# MCU-power.net
KiCad netlist of a schematic drawn in Altium Designer
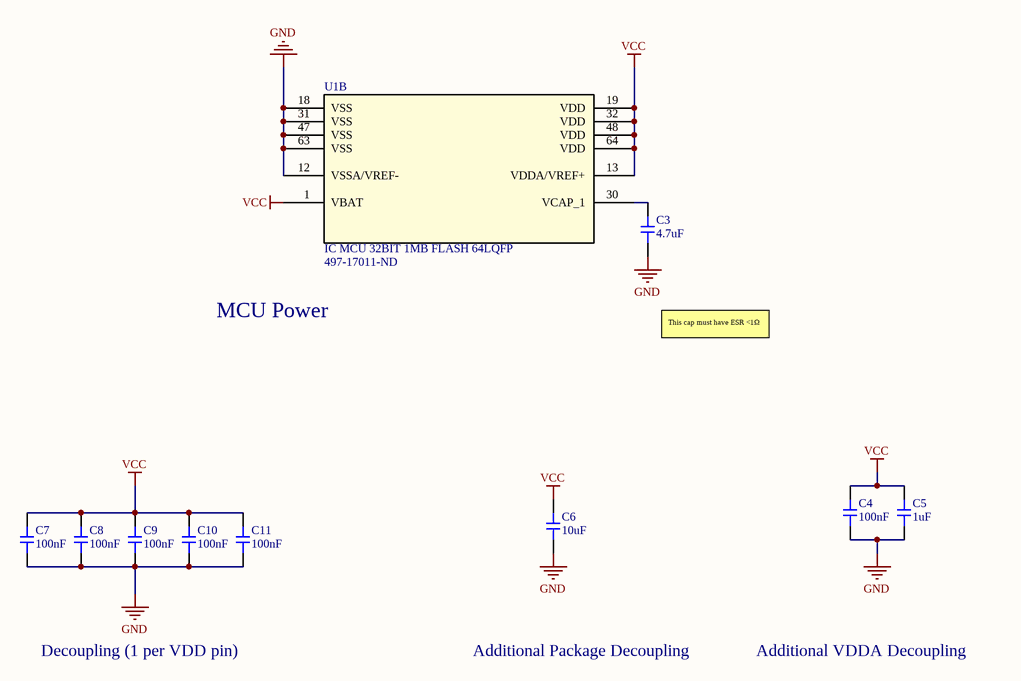
[diagram p0: MCU-power.SchDoc]

(export (version "E")
  (design (tool "Eeschema 10.0.6"))
  (components
    (comp (ref "C3")
      (value "CL10A475KO8NNNC")
      (footprint "CAP-0603")
      (description "Capacitor, Ceramic (MLCC), 4.7uF, ±10%, 16V, X5R, ±10%, SMD 0603")
      (fields
        (field (name "JLCPCB BASIC PART") "Yes")
        (field (name "JLCPCB PART NUMBER") "C19666")
        (field (name "CAPACITANCE") "4.7uF")
      )
      (libsource (lib "JLCCapacitor") (part "CL10A475KO8NNNC"))
    )
    (comp (ref "C4")
      (value "CC0603KRX7R9BB104")
      (footprint "CAP-0603")
      (description "Capacitor, Ceramic (MLCC), 100nF, ±10%, 50V, X7R, ±10%, SMD 0603")
      (fields
        (field (name "JLCPCB BASIC PART") "Yes")
        (field (name "CAPACITANCE") "100nF")
        (field (name "JLCPCB PART NUMBER") "C14663")
      )
      (libsource (lib "JLCCapacitor") (part "CC0603KRX7R9BB104"))
    )
    (comp (ref "C5")
      (value "CL10A105KB8NNNC")
      (footprint "CAP-0603")
      (description "Capacitor, Ceramic (MLCC), 1uF, ±10%, 50V, X5R, ±10%, SMD 0603")
      (fields
        (field (name "JLCPCB BASIC PART") "Yes")
        (field (name "JLCPCB PART NUMBER") "C15849")
        (field (name "CAPACITANCE") "1uF")
      )
      (libsource (lib "JLCCapacitor") (part "CL10A105KB8NNNC"))
    )
    (comp (ref "C6")
      (value "CL10A106KP8NNNC")
      (footprint "CAP-0603")
      (description "Capacitor, Ceramic (MLCC), 10uF, ±10%, 10V, X5R, ±10%, SMD 0603")
      (fields
        (field (name "JLCPCB BASIC PART") "Yes")
        (field (name "JLCPCB PART NUMBER") "C19702")
        (field (name "CAPACITANCE") "10uF")
      )
      (libsource (lib "JLCCapacitor") (part "CL10A106KP8NNNC"))
    )
    (comp (ref "C7")
      (value "CC0603KRX7R9BB104")
      (footprint "CAP-0603")
      (description "Capacitor, Ceramic (MLCC), 100nF, ±10%, 50V, X7R, ±10%, SMD 0603")
      (fields
        (field (name "JLCPCB BASIC PART") "Yes")
        (field (name "CAPACITANCE") "100nF")
        (field (name "JLCPCB PART NUMBER") "C14663")
      )
      (libsource (lib "JLCCapacitor") (part "CC0603KRX7R9BB104"))
    )
    (comp (ref "C8")
      (value "CC0603KRX7R9BB104")
      (footprint "CAP-0603")
      (description "Capacitor, Ceramic (MLCC), 100nF, ±10%, 50V, X7R, ±10%, SMD 0603")
      (fields
        (field (name "JLCPCB BASIC PART") "Yes")
        (field (name "CAPACITANCE") "100nF")
        (field (name "JLCPCB PART NUMBER") "C14663")
      )
      (libsource (lib "JLCCapacitor") (part "CC0603KRX7R9BB104"))
    )
    (comp (ref "C9")
      (value "CC0603KRX7R9BB104")
      (footprint "CAP-0603")
      (description "Capacitor, Ceramic (MLCC), 100nF, ±10%, 50V, X7R, ±10%, SMD 0603")
      (fields
        (field (name "JLCPCB BASIC PART") "Yes")
        (field (name "CAPACITANCE") "100nF")
        (field (name "JLCPCB PART NUMBER") "C14663")
      )
      (libsource (lib "JLCCapacitor") (part "CC0603KRX7R9BB104"))
    )
    (comp (ref "C10")
      (value "CC0603KRX7R9BB104")
      (footprint "CAP-0603")
      (description "Capacitor, Ceramic (MLCC), 100nF, ±10%, 50V, X7R, ±10%, SMD 0603")
      (fields
        (field (name "JLCPCB BASIC PART") "Yes")
        (field (name "CAPACITANCE") "100nF")
        (field (name "JLCPCB PART NUMBER") "C14663")
      )
      (libsource (lib "JLCCapacitor") (part "CC0603KRX7R9BB104"))
    )
    (comp (ref "C11")
      (value "CC0603KRX7R9BB104")
      (footprint "CAP-0603")
      (description "Capacitor, Ceramic (MLCC), 100nF, ±10%, 50V, X7R, ±10%, SMD 0603")
      (fields
        (field (name "JLCPCB BASIC PART") "Yes")
        (field (name "CAPACITANCE") "100nF")
        (field (name "JLCPCB PART NUMBER") "C14663")
      )
      (libsource (lib "JLCCapacitor") (part "CC0603KRX7R9BB104"))
    )
    (comp (ref "U1")
      (value "IC MCU 32BIT 1MB FLASH 64LQFP")
      (footprint "LQFP64-10x10mm")
      (description "ARM® Cortex®-M4 STM32F4 Microcontroller IC 32-Bit 100MHz 1MB (1M x 8) FLASH 64-LQFP (10x10)")
      (fields
        (field (name "MANUFACTURER_PART_NUMBER") "stm32f4xxr2")
        (field (name "SUPPLIER PART NUMBER 1") "497-17011-ND")
        (field (name "COPYRIGHT") "Copyright (C) 2016 Accelerated Designs. All rights reserved")
      )
      (libsource (lib "Misc") (part "STM32F4xxR2_minimalist"))
    )
  )
  (nets
    (net (code "1") (name "GND") (class "Default")
      (node (ref "C10") (pin "1") (pinfunction "1_1") (pintype "passive"))
      (node (ref "C11") (pin "1") (pinfunction "1_1") (pintype "passive"))
      (node (ref "C3") (pin "1") (pinfunction "1_1") (pintype "passive"))
      (node (ref "C4") (pin "1") (pinfunction "1_1") (pintype "passive"))
      (node (ref "C5") (pin "1") (pinfunction "1_1") (pintype "passive"))
      (node (ref "C6") (pin "1") (pinfunction "1_1") (pintype "passive"))
      (node (ref "C7") (pin "1") (pinfunction "1_1") (pintype "passive"))
      (node (ref "C8") (pin "1") (pinfunction "1_1") (pintype "passive"))
      (node (ref "C9") (pin "1") (pinfunction "1_1") (pintype "passive"))
      (node (ref "U1") (pin "12") (pinfunction "VSSA/VREF-_12") (pintype "power_in"))
      (node (ref "U1") (pin "18") (pinfunction "VSS_18") (pintype "power_in"))
      (node (ref "U1") (pin "31") (pinfunction "VSS_31") (pintype "power_in"))
      (node (ref "U1") (pin "47") (pinfunction "VSS_47") (pintype "power_in"))
      (node (ref "U1") (pin "63") (pinfunction "VSS_63") (pintype "power_in"))
    )
    (net (code "2") (name "Net-(U1B-VCAP_1)") (class "Default")
      (node (ref "C3") (pin "2") (pinfunction "2_2") (pintype "passive"))
      (node (ref "U1") (pin "30") (pinfunction "VCAP_1_30") (pintype "power_in"))
    )
    (net (code "3") (name "VCC") (class "Default")
      (node (ref "C10") (pin "2") (pinfunction "2_2") (pintype "passive"))
      (node (ref "C11") (pin "2") (pinfunction "2_2") (pintype "passive"))
      (node (ref "C4") (pin "2") (pinfunction "2_2") (pintype "passive"))
      (node (ref "C5") (pin "2") (pinfunction "2_2") (pintype "passive"))
      (node (ref "C6") (pin "2") (pinfunction "2_2") (pintype "passive"))
      (node (ref "C7") (pin "2") (pinfunction "2_2") (pintype "passive"))
      (node (ref "C8") (pin "2") (pinfunction "2_2") (pintype "passive"))
      (node (ref "C9") (pin "2") (pinfunction "2_2") (pintype "passive"))
      (node (ref "U1") (pin "1") (pinfunction "VBAT_1") (pintype "power_in"))
      (node (ref "U1") (pin "13") (pinfunction "VDDA/VREF+_13") (pintype "power_in"))
      (node (ref "U1") (pin "19") (pinfunction "VDD_19") (pintype "power_in"))
      (node (ref "U1") (pin "32") (pinfunction "VDD_32") (pintype "power_in"))
      (node (ref "U1") (pin "48") (pinfunction "VDD_48") (pintype "power_in"))
      (node (ref "U1") (pin "64") (pinfunction "VDD_64") (pintype "power_in"))
    )
  )
)
